# USB_Micro_Power_to_lab_board_2015-12-26.net
KiCad netlist of a schematic drawn in EAGLE
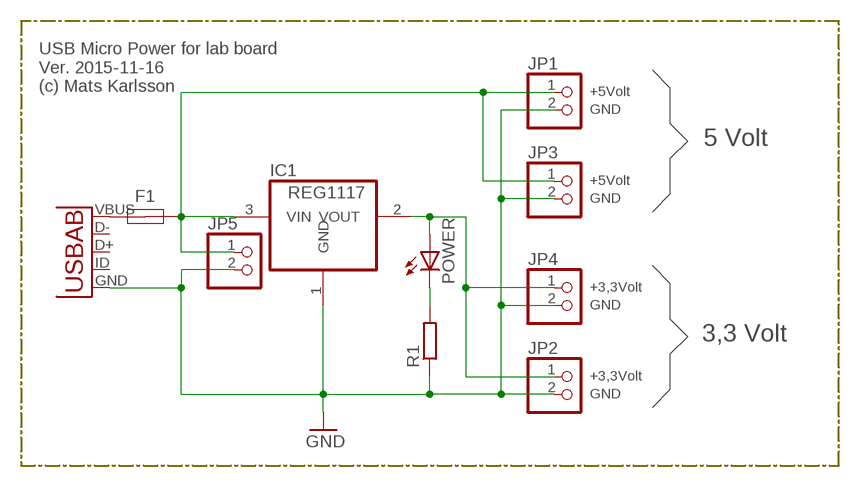
[diagram p0: schematic, sheet 1]

(export (version "E")
  (design (tool "Eeschema 10.0.6"))
  (components
    (comp (ref "F1")
      (value "LITTELFUSE_1812_500MA")
      (footprint "eagle-import:R1812")
      (fields (field (name "MPN") "1812L050PR"))
      (libsource (lib "eagle-import") (part "LITTELFUSE_1812_500MA"))
    )
    (comp (ref "IC1")
      (value "REG1117")
      (footprint "eagle-import:SOT223")
      (libsource (lib "eagle-import") (part "REG1117"))
    )
    (comp (ref "JP1")
      (value "PINHD-1X2")
      (footprint "eagle-import:1X02")
      (libsource (lib "eagle-import") (part "PINHD-1X2"))
    )
    (comp (ref "JP2")
      (value "PINHD-1X2")
      (footprint "eagle-import:1X02")
      (libsource (lib "eagle-import") (part "PINHD-1X2"))
    )
    (comp (ref "JP3")
      (value "PINHD-1X2")
      (footprint "eagle-import:1X02")
      (libsource (lib "eagle-import") (part "PINHD-1X2"))
    )
    (comp (ref "JP4")
      (value "PINHD-1X2")
      (footprint "eagle-import:1X02")
      (libsource (lib "eagle-import") (part "PINHD-1X2"))
    )
    (comp (ref "JP5")
      (value "PINHD-1X2")
      (footprint "eagle-import:1X02")
      (libsource (lib "eagle-import") (part "PINHD-1X2"))
    )
    (comp (ref "POWER")
      (value "LED3MM")
      (footprint "eagle-import:LED3MM")
      (libsource (lib "eagle-import") (part "LED3MM"))
    )
    (comp (ref "R1")
      (value "R-EU_0204/5")
      (footprint "eagle-import:0204_5")
      (libsource (lib "eagle-import") (part "R-EU_0204/5"))
    )
    (comp (ref "U1")
      (value "USB-ABUSB-AB-MICRO-SMD")
      (footprint "eagle-import:USB-AB-MICRO-SMD_VO2")
      (libsource (lib "eagle-import") (part "USB-ABUSB-AB-MICRO-SMD"))
    )
  )
  (nets
    (net (code "1") (name "GND") (class "Default")
      (node (ref "IC1") (pin "1") (pinfunction "GND_1") (pintype "power_in"))
      (node (ref "JP1") (pin "2") (pinfunction "2_2") (pintype "passive"))
      (node (ref "JP2") (pin "2") (pinfunction "2_2") (pintype "passive"))
      (node (ref "JP3") (pin "2") (pinfunction "2_2") (pintype "passive"))
      (node (ref "JP4") (pin "2") (pinfunction "2_2") (pintype "passive"))
      (node (ref "JP5") (pin "2") (pinfunction "2_2") (pintype "passive"))
      (node (ref "R1") (pin "1") (pinfunction "1_1") (pintype "passive"))
      (node (ref "U1") (pin "GND") (pinfunction "GND_GND") (pintype "bidirectional"))
    )
    (net (code "2") (name "Net-(F1-P$1)") (class "Default")
      (node (ref "F1") (pin "1") (pinfunction "P$1_1") (pintype "bidirectional"))
      (node (ref "U1") (pin "VBUS") (pinfunction "VBUS_VBUS") (pintype "bidirectional"))
    )
    (net (code "3") (name "Net-(F1-P$2)") (class "Default")
      (node (ref "F1") (pin "2") (pinfunction "P$2_2") (pintype "bidirectional"))
      (node (ref "IC1") (pin "3") (pinfunction "VIN_3") (pintype "input"))
      (node (ref "JP1") (pin "1") (pinfunction "1_1") (pintype "passive"))
      (node (ref "JP3") (pin "1") (pinfunction "1_1") (pintype "passive"))
      (node (ref "JP5") (pin "1") (pinfunction "1_1") (pintype "passive"))
    )
    (net (code "4") (name "Net-(IC1-VOUT)") (class "Default")
      (node (ref "IC1") (pin "2") (pinfunction "VOUT_2") (pintype "output"))
      (node (ref "JP2") (pin "1") (pinfunction "1_1") (pintype "passive"))
      (node (ref "JP4") (pin "1") (pinfunction "1_1") (pintype "passive"))
      (node (ref "POWER") (pin "A") (pinfunction "A_A") (pintype "passive"))
    )
    (net (code "5") (name "Net-(POWER-C)") (class "Default")
      (node (ref "POWER") (pin "K") (pinfunction "C_K") (pintype "passive"))
      (node (ref "R1") (pin "2") (pinfunction "2_2") (pintype "passive"))
    )
    (net (code "6") (name "unconnected-(U1-PadD+)") (class "Default")
      (node (ref "U1") (pin "D+") (pinfunction "D+_D+") (pintype "bidirectional"))
    )
    (net (code "7") (name "unconnected-(U1-PadD-)") (class "Default")
      (node (ref "U1") (pin "D-") (pinfunction "D-_D-") (pintype "bidirectional"))
    )
    (net (code "8") (name "unconnected-(U1-USBID-PadID)") (class "Default")
      (node (ref "U1") (pin "ID") (pinfunction "USBID_ID") (pintype "bidirectional"))
    )
  )
)
